# Sensor_PCI_Sch.net
KiCad netlist of a schematic drawn in Altium Designer
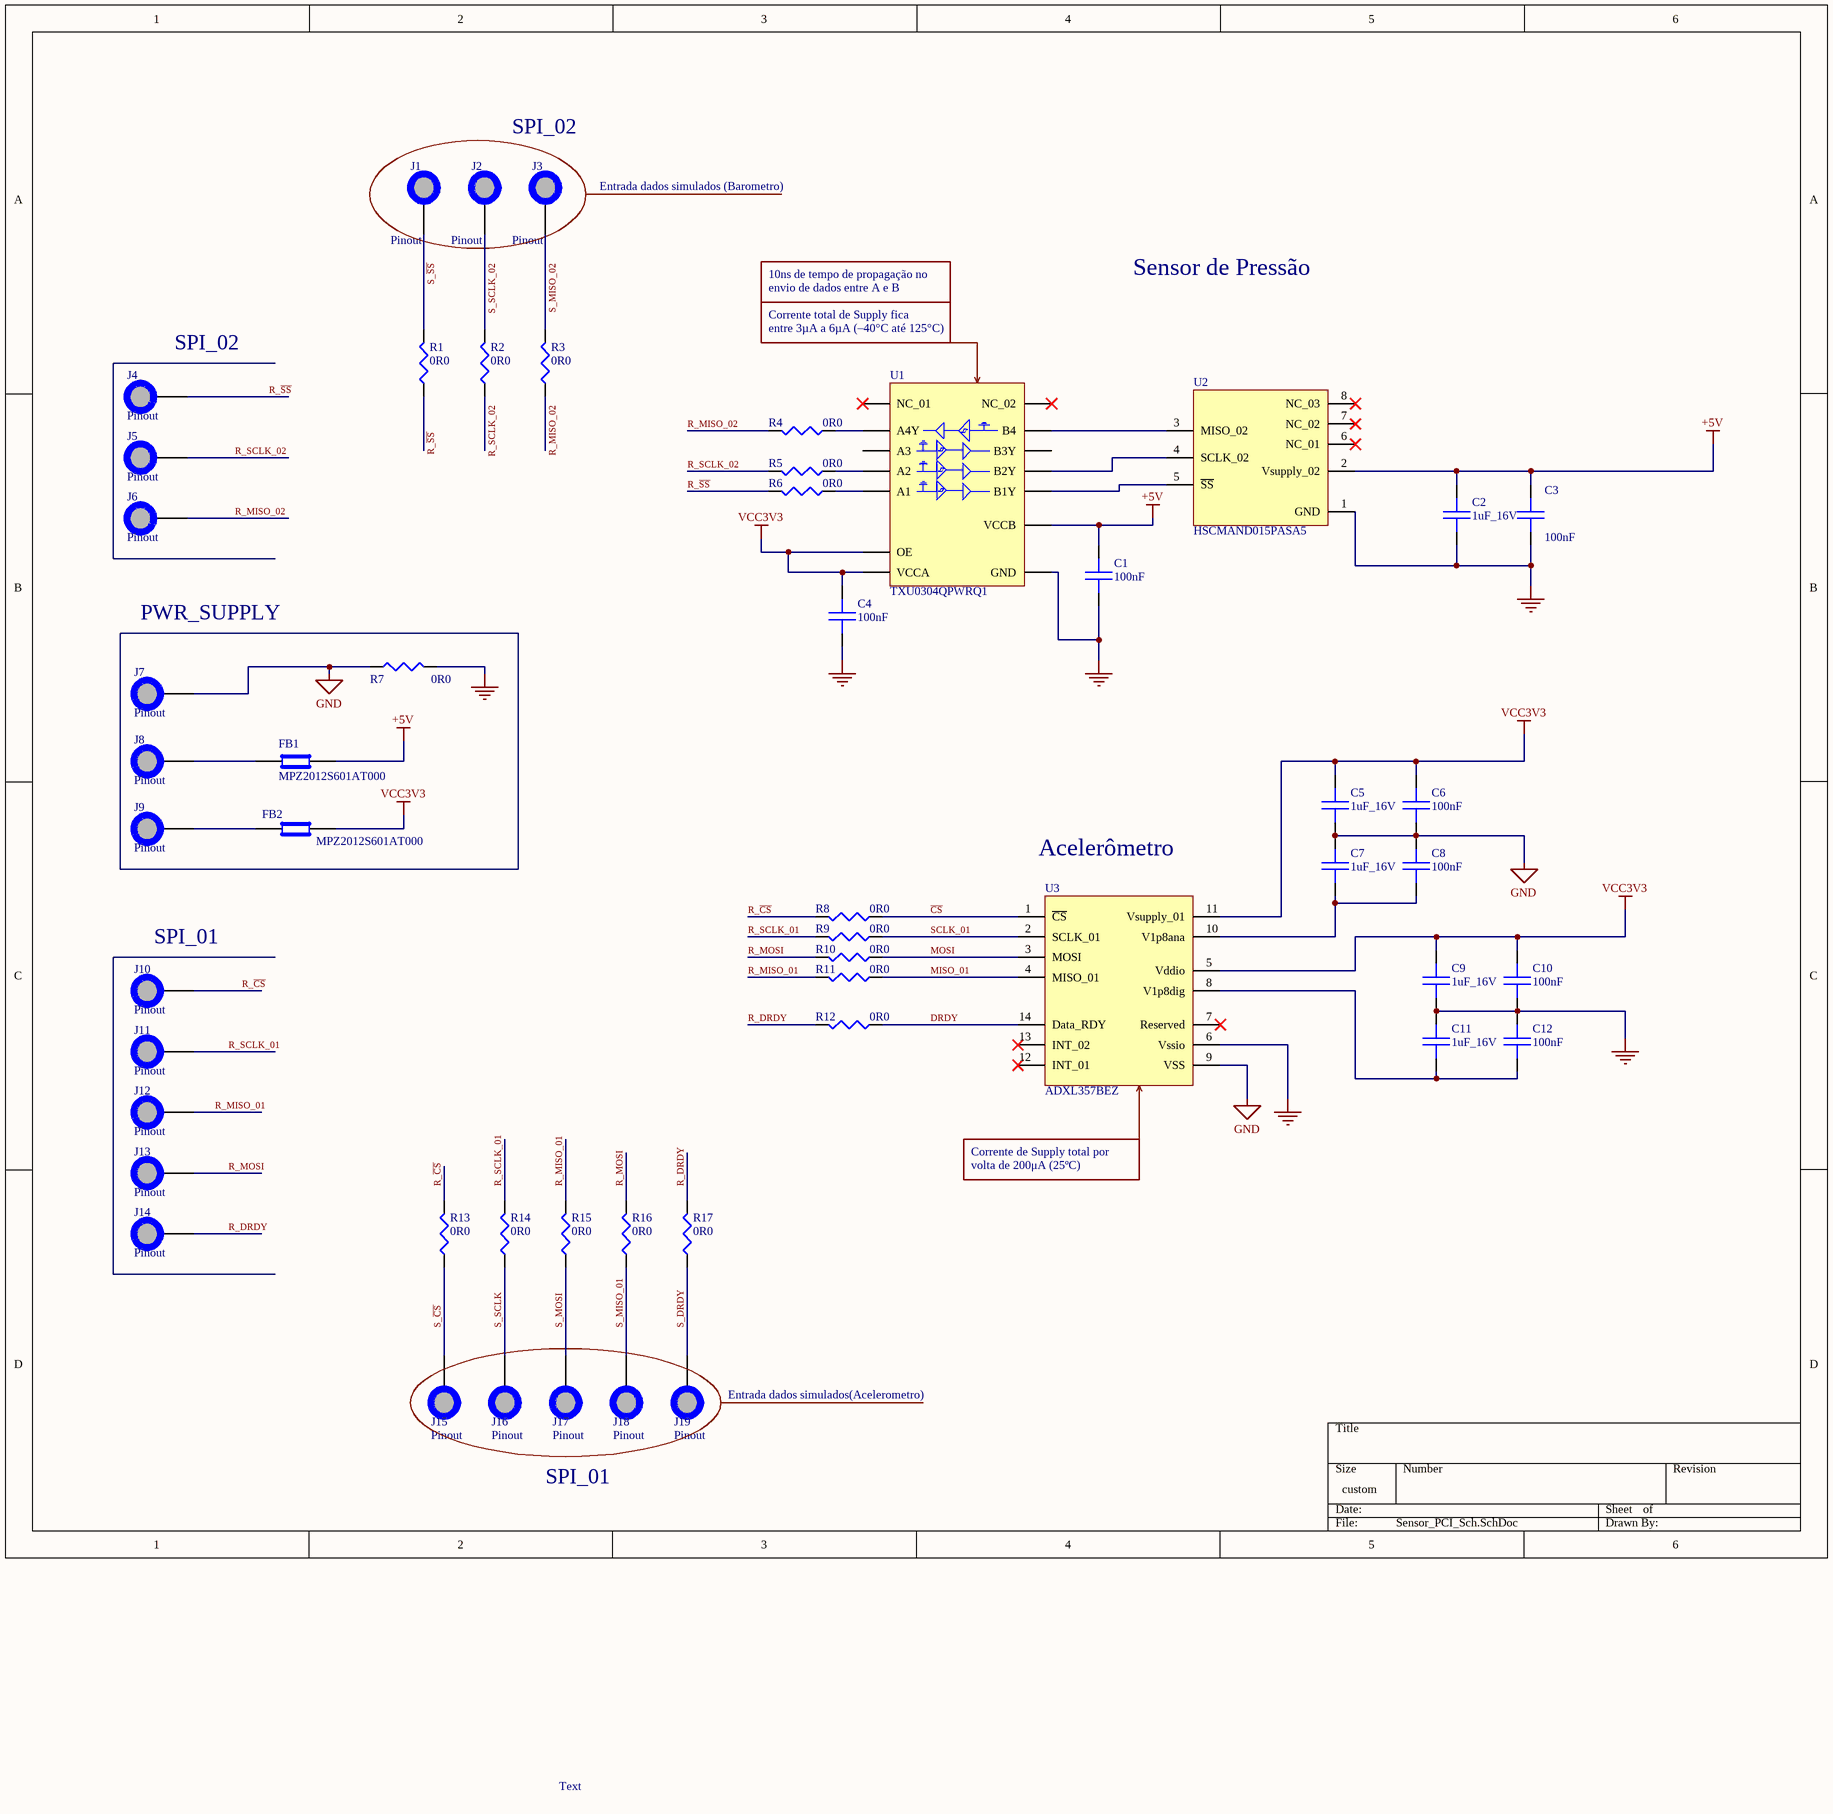
[diagram p0: Sensor_PCI_Sch.SchDoc]

(export (version "E")
  (design (tool "Eeschema 10.0.6"))
  (components
    (comp (ref "C1")
      (value "100nF")
      (footprint "CP_0805")
      (description "Cap Ceramic 0.1uF 50V X7R 20% Pad SMD 0805 150°C T/R")
      (fields
        (field (name "MANUFACTURER") "Vishay Vitramon")
        (field (name "MANUFACTURER PART NUMBER") "VJ0805Y104MXAMR")
      )
      (libsource (lib "Sensor_PCI_schlib") (part "C_0805_0.1uF"))
    )
    (comp (ref "C2")
      (value "1uF_16V")
      (footprint "C_1206")
      (description "Cap Ceramic 1uF 16V Y5V 20% SMD 1206 85°C Plastic T/R")
      (fields
        (field (name "MANUFACTURER") "Vishay Vitramon")
        (field (name "MANUFACTURER PART NUMBER") "VJ1206V105MXJTW1BC")
      )
      (libsource (lib "Sensor_PCI_schlib") (part "C_1206_1uF_16V"))
    )
    (comp (ref "C3")
      (value "100nF")
      (footprint "CP_0805")
      (description "Cap Ceramic 0.1uF 50V X7R 20% Pad SMD 0805 150°C T/R")
      (fields
        (field (name "MANUFACTURER") "Vishay Vitramon")
        (field (name "MANUFACTURER PART NUMBER") "VJ0805Y104MXAMR")
      )
      (libsource (lib "Sensor_PCI_schlib") (part "C_0805_0.1uF"))
    )
    (comp (ref "C4")
      (value "100nF")
      (footprint "CP_0805")
      (description "Cap Ceramic 0.1uF 50V X7R 20% Pad SMD 0805 150°C T/R")
      (fields
        (field (name "MANUFACTURER") "Vishay Vitramon")
        (field (name "MANUFACTURER PART NUMBER") "VJ0805Y104MXAMR")
      )
      (libsource (lib "Sensor_PCI_schlib") (part "C_0805_0.1uF"))
    )
    (comp (ref "C5")
      (value "1uF_16V")
      (footprint "C_1206")
      (description "Cap Ceramic 1uF 16V Y5V 20% SMD 1206 85°C Plastic T/R")
      (fields
        (field (name "MANUFACTURER") "Vishay Vitramon")
        (field (name "MANUFACTURER PART NUMBER") "VJ1206V105MXJTW1BC")
      )
      (libsource (lib "Sensor_PCI_schlib") (part "C_1206_1uF_16V"))
    )
    (comp (ref "C6")
      (value "100nF")
      (footprint "CP_0805")
      (description "Cap Ceramic 0.1uF 50V X7R 20% Pad SMD 0805 150°C T/R")
      (fields
        (field (name "MANUFACTURER") "Vishay Vitramon")
        (field (name "MANUFACTURER PART NUMBER") "VJ0805Y104MXAMR")
      )
      (libsource (lib "Sensor_PCI_schlib") (part "C_0805_0.1uF"))
    )
    (comp (ref "C7")
      (value "1uF_16V")
      (footprint "C_1206")
      (description "Cap Ceramic 1uF 16V Y5V 20% SMD 1206 85°C Plastic T/R")
      (fields
        (field (name "MANUFACTURER") "Vishay Vitramon")
        (field (name "MANUFACTURER PART NUMBER") "VJ1206V105MXJTW1BC")
      )
      (libsource (lib "Sensor_PCI_schlib") (part "C_1206_1uF_16V"))
    )
    (comp (ref "C8")
      (value "100nF")
      (footprint "CP_0805")
      (description "Cap Ceramic 0.1uF 50V X7R 20% Pad SMD 0805 150°C T/R")
      (fields
        (field (name "MANUFACTURER") "Vishay Vitramon")
        (field (name "MANUFACTURER PART NUMBER") "VJ0805Y104MXAMR")
      )
      (libsource (lib "Sensor_PCI_schlib") (part "C_0805_0.1uF"))
    )
    (comp (ref "C9")
      (value "1uF_16V")
      (footprint "C_1206")
      (description "Cap Ceramic 1uF 16V Y5V 20% SMD 1206 85°C Plastic T/R")
      (fields
        (field (name "MANUFACTURER") "Vishay Vitramon")
        (field (name "MANUFACTURER PART NUMBER") "VJ1206V105MXJTW1BC")
      )
      (libsource (lib "Sensor_PCI_schlib") (part "C_1206_1uF_16V"))
    )
    (comp (ref "C10")
      (value "100nF")
      (footprint "CP_0805")
      (description "Cap Ceramic 0.1uF 50V X7R 20% Pad SMD 0805 150°C T/R")
      (fields
        (field (name "MANUFACTURER") "Vishay Vitramon")
        (field (name "MANUFACTURER PART NUMBER") "VJ0805Y104MXAMR")
      )
      (libsource (lib "Sensor_PCI_schlib") (part "C_0805_0.1uF"))
    )
    (comp (ref "C11")
      (value "1uF_16V")
      (footprint "C_1206")
      (description "Cap Ceramic 1uF 16V Y5V 20% SMD 1206 85°C Plastic T/R")
      (fields
        (field (name "MANUFACTURER") "Vishay Vitramon")
        (field (name "MANUFACTURER PART NUMBER") "VJ1206V105MXJTW1BC")
      )
      (libsource (lib "Sensor_PCI_schlib") (part "C_1206_1uF_16V"))
    )
    (comp (ref "C12")
      (value "100nF")
      (footprint "CP_0805")
      (description "Cap Ceramic 0.1uF 50V X7R 20% Pad SMD 0805 150°C T/R")
      (fields
        (field (name "MANUFACTURER") "Vishay Vitramon")
        (field (name "MANUFACTURER PART NUMBER") "VJ0805Y104MXAMR")
      )
      (libsource (lib "Sensor_PCI_schlib") (part "C_0805_0.1uF"))
    )
    (comp (ref "FB1")
      (value "MPZ2012S601AT000")
      (footprint "CP_0805")
      (description "0805 600Ω ±25% DCR=0.1Ω 2A")
      (fields (field (name "MANUFACTURER") "TDK"))
      (libsource (lib "Sensor_PCI_schlib") (part "MPZ2012S601AT000"))
    )
    (comp (ref "FB2")
      (value "MPZ2012S601AT000")
      (footprint "CP_0805")
      (description "0805 600Ω ±25% DCR=0.1Ω 2A")
      (fields (field (name "MANUFACTURER") "TDK"))
      (libsource (lib "Sensor_PCI_schlib") (part "MPZ2012S601AT000"))
    )
    (comp (ref "J1")
      (value "Pinout")
      (footprint "Pinout")
      (libsource (lib "Sensor_PCI_schlib") (part "Pinout"))
    )
    (comp (ref "J2")
      (value "Pinout")
      (footprint "Pinout")
      (libsource (lib "Sensor_PCI_schlib") (part "Pinout"))
    )
    (comp (ref "J3")
      (value "Pinout")
      (footprint "Pinout")
      (libsource (lib "Sensor_PCI_schlib") (part "Pinout"))
    )
    (comp (ref "J4")
      (value "Pinout")
      (footprint "Pinout")
      (libsource (lib "Sensor_PCI_schlib") (part "Pinout"))
    )
    (comp (ref "J5")
      (value "Pinout")
      (footprint "Pinout")
      (libsource (lib "Sensor_PCI_schlib") (part "Pinout"))
    )
    (comp (ref "J6")
      (value "Pinout")
      (footprint "Pinout")
      (libsource (lib "Sensor_PCI_schlib") (part "Pinout"))
    )
    (comp (ref "J7")
      (value "Pinout")
      (footprint "Pinout")
      (libsource (lib "Sensor_PCI_schlib") (part "Pinout"))
    )
    (comp (ref "J8")
      (value "Pinout")
      (footprint "Pinout")
      (libsource (lib "Sensor_PCI_schlib") (part "Pinout"))
    )
    (comp (ref "J9")
      (value "Pinout")
      (footprint "Pinout")
      (libsource (lib "Sensor_PCI_schlib") (part "Pinout"))
    )
    (comp (ref "J10")
      (value "Pinout")
      (footprint "Pinout")
      (libsource (lib "Sensor_PCI_schlib") (part "Pinout"))
    )
    (comp (ref "J11")
      (value "Pinout")
      (footprint "Pinout")
      (libsource (lib "Sensor_PCI_schlib") (part "Pinout"))
    )
    (comp (ref "J12")
      (value "Pinout")
      (footprint "Pinout")
      (libsource (lib "Sensor_PCI_schlib") (part "Pinout"))
    )
    (comp (ref "J13")
      (value "Pinout")
      (footprint "Pinout")
      (libsource (lib "Sensor_PCI_schlib") (part "Pinout"))
    )
    (comp (ref "J14")
      (value "Pinout")
      (footprint "Pinout")
      (libsource (lib "Sensor_PCI_schlib") (part "Pinout"))
    )
    (comp (ref "J15")
      (value "Pinout")
      (footprint "Pinout")
      (libsource (lib "Sensor_PCI_schlib") (part "Pinout"))
    )
    (comp (ref "J16")
      (value "Pinout")
      (footprint "Pinout")
      (libsource (lib "Sensor_PCI_schlib") (part "Pinout"))
    )
    (comp (ref "J17")
      (value "Pinout")
      (footprint "Pinout")
      (libsource (lib "Sensor_PCI_schlib") (part "Pinout"))
    )
    (comp (ref "J18")
      (value "Pinout")
      (footprint "Pinout")
      (libsource (lib "Sensor_PCI_schlib") (part "Pinout"))
    )
    (comp (ref "J19")
      (value "Pinout")
      (footprint "Pinout")
      (libsource (lib "Sensor_PCI_schlib") (part "Pinout"))
    )
    (comp (ref "R1")
      (value "0R0")
      (footprint "R_0805")
      (description "CRCW Thick Film Commodity Chip Resistor Jumper 0805 Size 0 Ohm 0.125 W 2-Pin SMD Paper T/R")
      (fields
        (field (name "MANUFACTURER") "Vishay Dale")
        (field (name "MANUFACTURER PART NUMBER") "CRCW08050000Z0ECC")
      )
      (libsource (lib "Sensor_PCI_schlib") (part "Res_0805_0R0"))
    )
    (comp (ref "R2")
      (value "0R0")
      (footprint "R_0805")
      (description "CRCW Thick Film Commodity Chip Resistor Jumper 0805 Size 0 Ohm 0.125 W 2-Pin SMD Paper T/R")
      (fields
        (field (name "MANUFACTURER") "Vishay Dale")
        (field (name "MANUFACTURER PART NUMBER") "CRCW08050000Z0ECC")
      )
      (libsource (lib "Sensor_PCI_schlib") (part "Res_0805_0R0"))
    )
    (comp (ref "R3")
      (value "0R0")
      (footprint "R_0805")
      (description "CRCW Thick Film Commodity Chip Resistor Jumper 0805 Size 0 Ohm 0.125 W 2-Pin SMD Paper T/R")
      (fields
        (field (name "MANUFACTURER") "Vishay Dale")
        (field (name "MANUFACTURER PART NUMBER") "CRCW08050000Z0ECC")
      )
      (libsource (lib "Sensor_PCI_schlib") (part "Res_0805_0R0"))
    )
    (comp (ref "R4")
      (value "0R0")
      (footprint "R_0805")
      (description "CRCW Thick Film Commodity Chip Resistor Jumper 0805 Size 0 Ohm 0.125 W 2-Pin SMD Paper T/R")
      (fields
        (field (name "MANUFACTURER") "Vishay Dale")
        (field (name "MANUFACTURER PART NUMBER") "CRCW08050000Z0ECC")
      )
      (libsource (lib "Sensor_PCI_schlib") (part "Res_0805_0R0"))
    )
    (comp (ref "R5")
      (value "0R0")
      (footprint "R_0805")
      (description "CRCW Thick Film Commodity Chip Resistor Jumper 0805 Size 0 Ohm 0.125 W 2-Pin SMD Paper T/R")
      (fields
        (field (name "MANUFACTURER") "Vishay Dale")
        (field (name "MANUFACTURER PART NUMBER") "CRCW08050000Z0ECC")
      )
      (libsource (lib "Sensor_PCI_schlib") (part "Res_0805_0R0"))
    )
    (comp (ref "R6")
      (value "0R0")
      (footprint "R_0805")
      (description "CRCW Thick Film Commodity Chip Resistor Jumper 0805 Size 0 Ohm 0.125 W 2-Pin SMD Paper T/R")
      (fields
        (field (name "MANUFACTURER") "Vishay Dale")
        (field (name "MANUFACTURER PART NUMBER") "CRCW08050000Z0ECC")
      )
      (libsource (lib "Sensor_PCI_schlib") (part "Res_0805_0R0"))
    )
    (comp (ref "R7")
      (value "0R0")
      (footprint "R_0805")
      (description "CRCW Thick Film Commodity Chip Resistor Jumper 0805 Size 0 Ohm 0.125 W 2-Pin SMD Paper T/R")
      (fields
        (field (name "MANUFACTURER") "Vishay Dale")
        (field (name "MANUFACTURER PART NUMBER") "CRCW08050000Z0ECC")
      )
      (libsource (lib "Sensor_PCI_schlib") (part "Res_0805_0R0"))
    )
    (comp (ref "R8")
      (value "0R0")
      (footprint "R_0805")
      (description "CRCW Thick Film Commodity Chip Resistor Jumper 0805 Size 0 Ohm 0.125 W 2-Pin SMD Paper T/R")
      (fields
        (field (name "MANUFACTURER") "Vishay Dale")
        (field (name "MANUFACTURER PART NUMBER") "CRCW08050000Z0ECC")
      )
      (libsource (lib "Sensor_PCI_schlib") (part "Res_0805_0R0"))
    )
    (comp (ref "R9")
      (value "0R0")
      (footprint "R_0805")
      (description "CRCW Thick Film Commodity Chip Resistor Jumper 0805 Size 0 Ohm 0.125 W 2-Pin SMD Paper T/R")
      (fields
        (field (name "MANUFACTURER") "Vishay Dale")
        (field (name "MANUFACTURER PART NUMBER") "CRCW08050000Z0ECC")
      )
      (libsource (lib "Sensor_PCI_schlib") (part "Res_0805_0R0"))
    )
    (comp (ref "R10")
      (value "0R0")
      (footprint "R_0805")
      (description "CRCW Thick Film Commodity Chip Resistor Jumper 0805 Size 0 Ohm 0.125 W 2-Pin SMD Paper T/R")
      (fields
        (field (name "MANUFACTURER") "Vishay Dale")
        (field (name "MANUFACTURER PART NUMBER") "CRCW08050000Z0ECC")
      )
      (libsource (lib "Sensor_PCI_schlib") (part "Res_0805_0R0"))
    )
    (comp (ref "R11")
      (value "0R0")
      (footprint "R_0805")
      (description "CRCW Thick Film Commodity Chip Resistor Jumper 0805 Size 0 Ohm 0.125 W 2-Pin SMD Paper T/R")
      (fields
        (field (name "MANUFACTURER") "Vishay Dale")
        (field (name "MANUFACTURER PART NUMBER") "CRCW08050000Z0ECC")
      )
      (libsource (lib "Sensor_PCI_schlib") (part "Res_0805_0R0"))
    )
    (comp (ref "R12")
      (value "0R0")
      (footprint "R_0805")
      (description "CRCW Thick Film Commodity Chip Resistor Jumper 0805 Size 0 Ohm 0.125 W 2-Pin SMD Paper T/R")
      (fields
        (field (name "MANUFACTURER") "Vishay Dale")
        (field (name "MANUFACTURER PART NUMBER") "CRCW08050000Z0ECC")
      )
      (libsource (lib "Sensor_PCI_schlib") (part "Res_0805_0R0"))
    )
    (comp (ref "R13")
      (value "0R0")
      (footprint "R_0805")
      (description "CRCW Thick Film Commodity Chip Resistor Jumper 0805 Size 0 Ohm 0.125 W 2-Pin SMD Paper T/R")
      (fields
        (field (name "MANUFACTURER") "Vishay Dale")
        (field (name "MANUFACTURER PART NUMBER") "CRCW08050000Z0ECC")
      )
      (libsource (lib "Sensor_PCI_schlib") (part "Res_0805_0R0"))
    )
    (comp (ref "R14")
      (value "0R0")
      (footprint "R_0805")
      (description "CRCW Thick Film Commodity Chip Resistor Jumper 0805 Size 0 Ohm 0.125 W 2-Pin SMD Paper T/R")
      (fields
        (field (name "MANUFACTURER") "Vishay Dale")
        (field (name "MANUFACTURER PART NUMBER") "CRCW08050000Z0ECC")
      )
      (libsource (lib "Sensor_PCI_schlib") (part "Res_0805_0R0"))
    )
    (comp (ref "R15")
      (value "0R0")
      (footprint "R_0805")
      (description "CRCW Thick Film Commodity Chip Resistor Jumper 0805 Size 0 Ohm 0.125 W 2-Pin SMD Paper T/R")
      (fields
        (field (name "MANUFACTURER") "Vishay Dale")
        (field (name "MANUFACTURER PART NUMBER") "CRCW08050000Z0ECC")
      )
      (libsource (lib "Sensor_PCI_schlib") (part "Res_0805_0R0"))
    )
    (comp (ref "R16")
      (value "0R0")
      (footprint "R_0805")
      (description "CRCW Thick Film Commodity Chip Resistor Jumper 0805 Size 0 Ohm 0.125 W 2-Pin SMD Paper T/R")
      (fields
        (field (name "MANUFACTURER") "Vishay Dale")
        (field (name "MANUFACTURER PART NUMBER") "CRCW08050000Z0ECC")
      )
      (libsource (lib "Sensor_PCI_schlib") (part "Res_0805_0R0"))
    )
    (comp (ref "R17")
      (value "0R0")
      (footprint "R_0805")
      (description "CRCW Thick Film Commodity Chip Resistor Jumper 0805 Size 0 Ohm 0.125 W 2-Pin SMD Paper T/R")
      (fields
        (field (name "MANUFACTURER") "Vishay Dale")
        (field (name "MANUFACTURER PART NUMBER") "CRCW08050000Z0ECC")
      )
      (libsource (lib "Sensor_PCI_schlib") (part "Res_0805_0R0"))
    )
    (comp (ref "U1")
      (value "TXU0304QPWRQ1")
      (footprint "TSSOP-PW")
      (description "Automotive four channel unidirectional level shifter 14-TSSOP -40 to 125")
      (fields (field (name "MANUFACTURER") "Texas Instruments"))
      (libsource (lib "Sensor_PCI_schlib") (part "Tradutor fixo de Tensão-SPI"))
    )
    (comp (ref "U2")
      (value "HSCMAND015PASA5")
      (footprint "SMT_08_2.54mm")
      (description "Board Mount Pressure Sensors SMT, Single Ax Barbed Absolute, 5V")
      (fields (field (name "MANUFACTURER") "Honeywell Sensing & Control"))
      (libsource (lib "Sensor_PCI_schlib") (part "Sensor_Pressão"))
    )
    (comp (ref "U3")
      (value "ADXL357BEZ")
      (footprint "Quad_14_1.2mm")
      (description "Accelerometer Tri-axis Digital Accel")
      (fields (field (name "MANUFACTURER") "Analog Devices"))
      (libsource (lib "Sensor_PCI_schlib") (part "Acelerômetro"))
    )
  )
  (nets
    (net (code "1") (name "+5V") (class "Default")
      (node (ref "C1") (pin "2") (pinfunction "2_2") (pintype "passive"))
      (node (ref "C2") (pin "1") (pinfunction "3_1") (pintype "passive"))
      (node (ref "C3") (pin "2") (pinfunction "2_2") (pintype "passive"))
      (node (ref "FB1") (pin "2") (pinfunction "2_2") (pintype "passive"))
      (node (ref "U1") (pin "14") (pinfunction "VCCB_14") (pintype "passive"))
      (node (ref "U2") (pin "2") (pinfunction "Vsupply_02_2") (pintype "passive"))
    )
    (net (code "2") (name "/DRDY") (class "Default")
      (node (ref "R12") (pin "1") (pinfunction "1_1") (pintype "passive"))
      (node (ref "U3") (pin "14") (pinfunction "Data_RDY_14") (pintype "passive"))
    )
    (net (code "3") (name "/MISO_01") (class "Default")
      (node (ref "R11") (pin "1") (pinfunction "1_1") (pintype "passive"))
      (node (ref "U3") (pin "4") (pinfunction "MISO_01_4") (pintype "passive"))
    )
    (net (code "4") (name "/MOSI") (class "Default")
      (node (ref "R10") (pin "1") (pinfunction "1_1") (pintype "passive"))
      (node (ref "U3") (pin "3") (pinfunction "MOSI_3") (pintype "passive"))
    )
    (net (code "5") (name "/R_DRDY") (class "Default")
      (node (ref "J14") (pin "1") (pinfunction "1_1") (pintype "passive"))
      (node (ref "R12") (pin "2") (pinfunction "2_2") (pintype "passive"))
      (node (ref "R17") (pin "2") (pinfunction "2_2") (pintype "passive"))
    )
    (net (code "6") (name "/R_MISO_01") (class "Default")
      (node (ref "J12") (pin "1") (pinfunction "1_1") (pintype "passive"))
      (node (ref "R11") (pin "2") (pinfunction "2_2") (pintype "passive"))
      (node (ref "R15") (pin "2") (pinfunction "2_2") (pintype "passive"))
    )
    (net (code "7") (name "/R_MISO_02") (class "Default")
      (node (ref "J6") (pin "1") (pinfunction "1_1") (pintype "passive"))
      (node (ref "R3") (pin "1") (pinfunction "1_1") (pintype "passive"))
      (node (ref "R4") (pin "2") (pinfunction "2_2") (pintype "passive"))
    )
    (net (code "8") (name "/R_MOSI") (class "Default")
      (node (ref "J13") (pin "1") (pinfunction "1_1") (pintype "passive"))
      (node (ref "R10") (pin "2") (pinfunction "2_2") (pintype "passive"))
      (node (ref "R16") (pin "2") (pinfunction "2_2") (pintype "passive"))
    )
    (net (code "9") (name "/R_SCLK_01") (class "Default")
      (node (ref "J11") (pin "1") (pinfunction "1_1") (pintype "passive"))
      (node (ref "R14") (pin "2") (pinfunction "2_2") (pintype "passive"))
      (node (ref "R9") (pin "2") (pinfunction "2_2") (pintype "passive"))
    )
    (net (code "10") (name "/R_SCLK_02") (class "Default")
      (node (ref "J5") (pin "1") (pinfunction "1_1") (pintype "passive"))
      (node (ref "R2") (pin "1") (pinfunction "1_1") (pintype "passive"))
      (node (ref "R5") (pin "2") (pinfunction "2_2") (pintype "passive"))
    )
    (net (code "11") (name "/R_~{CS}") (class "Default")
      (node (ref "J10") (pin "1") (pinfunction "1_1") (pintype "passive"))
      (node (ref "R13") (pin "2") (pinfunction "2_2") (pintype "passive"))
      (node (ref "R8") (pin "2") (pinfunction "2_2") (pintype "passive"))
    )
    (net (code "12") (name "/R_~{SS}") (class "Default")
      (node (ref "J4") (pin "1") (pinfunction "1_1") (pintype "passive"))
      (node (ref "R1") (pin "1") (pinfunction "1_1") (pintype "passive"))
      (node (ref "R6") (pin "2") (pinfunction "2_2") (pintype "passive"))
    )
    (net (code "13") (name "/SCLK_01") (class "Default")
      (node (ref "R9") (pin "1") (pinfunction "1_1") (pintype "passive"))
      (node (ref "U3") (pin "2") (pinfunction "SCLK_01_2") (pintype "passive"))
    )
    (net (code "14") (name "/S_DRDY") (class "Default")
      (node (ref "J19") (pin "1") (pinfunction "1_1") (pintype "passive"))
      (node (ref "R17") (pin "1") (pinfunction "1_1") (pintype "passive"))
    )
    (net (code "15") (name "/S_MISO_01") (class "Default")
      (node (ref "J18") (pin "1") (pinfunction "1_1") (pintype "passive"))
      (node (ref "R16") (pin "1") (pinfunction "1_1") (pintype "passive"))
    )
    (net (code "16") (name "/S_MISO_02") (class "Default")
      (node (ref "J3") (pin "1") (pinfunction "1_1") (pintype "passive"))
      (node (ref "R3") (pin "2") (pinfunction "2_2") (pintype "passive"))
    )
    (net (code "17") (name "/S_MOSI") (class "Default")
      (node (ref "J17") (pin "1") (pinfunction "1_1") (pintype "passive"))
      (node (ref "R15") (pin "1") (pinfunction "1_1") (pintype "passive"))
    )
    (net (code "18") (name "/S_SCLK") (class "Default")
      (node (ref "J16") (pin "1") (pinfunction "1_1") (pintype "passive"))
      (node (ref "R14") (pin "1") (pinfunction "1_1") (pintype "passive"))
    )
    (net (code "19") (name "/S_SCLK_02") (class "Default")
      (node (ref "J2") (pin "1") (pinfunction "1_1") (pintype "passive"))
      (node (ref "R2") (pin "2") (pinfunction "2_2") (pintype "passive"))
    )
    (net (code "20") (name "/S_~{CS}") (class "Default")
      (node (ref "J15") (pin "1") (pinfunction "1_1") (pintype "passive"))
      (node (ref "R13") (pin "1") (pinfunction "1_1") (pintype "passive"))
    )
    (net (code "21") (name "/S_~{SS}") (class "Default")
      (node (ref "J1") (pin "1") (pinfunction "1_1") (pintype "passive"))
      (node (ref "R1") (pin "2") (pinfunction "2_2") (pintype "passive"))
    )
    (net (code "22") (name "/~{CS}") (class "Default")
      (node (ref "R8") (pin "1") (pinfunction "1_1") (pintype "passive"))
      (node (ref "U3") (pin "1") (pinfunction "~{CS}_1") (pintype "passive"))
    )
    (net (code "23") (name "GND") (class "Default")
      (node (ref "C1") (pin "1") (pinfunction "1_1") (pintype "passive"))
      (node (ref "C10") (pin "1") (pinfunction "1_1") (pintype "passive"))
      (node (ref "C11") (pin "1") (pinfunction "3_1") (pintype "passive"))
      (node (ref "C12") (pin "2") (pinfunction "2_2") (pintype "passive"))
      (node (ref "C2") (pin "2") (pinfunction "4_2") (pintype "passive"))
      (node (ref "C3") (pin "1") (pinfunction "1_1") (pintype "passive"))
      (node (ref "C4") (pin "1") (pinfunction "1_1") (pintype "passive"))
      (node (ref "C5") (pin "2") (pinfunction "4_2") (pintype "passive"))
      (node (ref "C6") (pin "1") (pinfunction "1_1") (pintype "passive"))
      (node (ref "C7") (pin "1") (pinfunction "3_1") (pintype "passive"))
      (node (ref "C8") (pin "2") (pinfunction "2_2") (pintype "passive"))
      (node (ref "C9") (pin "2") (pinfunction "4_2") (pintype "passive"))
      (node (ref "J7") (pin "1") (pinfunction "1_1") (pintype "passive"))
      (node (ref "R7") (pin "1") (pinfunction "1_1") (pintype "passive"))
      (node (ref "R7") (pin "2") (pinfunction "2_2") (pintype "passive"))
      (node (ref "U1") (pin "7") (pinfunction "GND_7") (pintype "passive"))
      (node (ref "U2") (pin "1") (pinfunction "GND_1") (pintype "passive"))
      (node (ref "U3") (pin "6") (pinfunction "Vssio_6") (pintype "passive"))
      (node (ref "U3") (pin "9") (pinfunction "VSS_9") (pintype "passive"))
    )
    (net (code "24") (name "Net-(C7-4)") (class "Default")
      (node (ref "C7") (pin "2") (pinfunction "4_2") (pintype "passive"))
      (node (ref "C8") (pin "1") (pinfunction "1_1") (pintype "passive"))
      (node (ref "U3") (pin "10") (pinfunction "V1p8ana_10") (pintype "passive"))
    )
    (net (code "25") (name "Net-(C11-4)") (class "Default")
      (node (ref "C11") (pin "2") (pinfunction "4_2") (pintype "passive"))
      (node (ref "C12") (pin "1") (pinfunction "1_1") (pintype "passive"))
      (node (ref "U3") (pin "8") (pinfunction "V1p8dig_8") (pintype "passive"))
    )
    (net (code "26") (name "Net-(FB1-Pad1)") (class "Default")
      (node (ref "FB1") (pin "1") (pinfunction "1_1") (pintype "passive"))
      (node (ref "J8") (pin "1") (pinfunction "1_1") (pintype "passive"))
    )
    (net (code "27") (name "Net-(FB2-Pad1)") (class "Default")
      (node (ref "FB2") (pin "1") (pinfunction "1_1") (pintype "passive"))
      (node (ref "J9") (pin "1") (pinfunction "1_1") (pintype "passive"))
    )
    (net (code "28") (name "Net-(U1-A1)") (class "Default")
      (node (ref "R6") (pin "1") (pinfunction "1_1") (pintype "passive"))
      (node (ref "U1") (pin "2") (pinfunction "A1_2") (pintype "passive"))
    )
    (net (code "29") (name "Net-(U1-A2)") (class "Default")
      (node (ref "R5") (pin "1") (pinfunction "1_1") (pintype "passive"))
      (node (ref "U1") (pin "3") (pinfunction "A2_3") (pintype "passive"))
    )
    (net (code "30") (name "Net-(U1-A4Y)") (class "Default")
      (node (ref "R4") (pin "1") (pinfunction "1_1") (pintype "passive"))
      (node (ref "U1") (pin "5") (pinfunction "A4Y_5") (pintype "passive"))
    )
    (net (code "31") (name "Net-(U1-B1Y)") (class "Default")
      (node (ref "U1") (pin "13") (pinfunction "B1Y_13") (pintype "passive"))
      (node (ref "U2") (pin "5") (pinfunction "~{SS}_5") (pintype "passive"))
    )
    (net (code "32") (name "Net-(U1-B2Y)") (class "Default")
      (node (ref "U1") (pin "12") (pinfunction "B2Y_12") (pintype "passive"))
      (node (ref "U2") (pin "4") (pinfunction "SCLK_02_4") (pintype "passive"))
    )
    (net (code "33") (name "Net-(U1-B4)") (class "Default")
      (node (ref "U1") (pin "10") (pinfunction "B4_10") (pintype "passive"))
      (node (ref "U2") (pin "3") (pinfunction "MISO_02_3") (pintype "passive"))
    )
    (net (code "34") (name "VCC3V3") (class "Default")
      (node (ref "C10") (pin "2") (pinfunction "2_2") (pintype "passive"))
      (node (ref "C4") (pin "2") (pinfunction "2_2") (pintype "passive"))
      (node (ref "C5") (pin "1") (pinfunction "3_1") (pintype "passive"))
      (node (ref "C6") (pin "2") (pinfunction "2_2") (pintype "passive"))
      (node (ref "C9") (pin "1") (pinfunction "3_1") (pintype "passive"))
      (node (ref "FB2") (pin "2") (pinfunction "2_2") (pintype "passive"))
      (node (ref "U1") (pin "1") (pinfunction "VCCA_1") (pintype "passive"))
      (node (ref "U1") (pin "8") (pinfunction "OE_8") (pintype "passive"))
      (node (ref "U3") (pin "11") (pinfunction "Vsupply_01_11") (pintype "passive"))
      (node (ref "U3") (pin "5") (pinfunction "Vddio_5") (pintype "passive"))
    )
    (net (code "35") (name "unconnected-(U1-A3-Pad4)") (class "Default")
      (node (ref "U1") (pin "4") (pinfunction "A3_4") (pintype "passive"))
    )
    (net (code "36") (name "unconnected-(U1-B3Y-Pad11)") (class "Default")
      (node (ref "U1") (pin "11") (pinfunction "B3Y_11") (pintype "passive"))
    )
    (net (code "37") (name "unconnected-(U1-NC_01-Pad6)") (class "Default")
      (node (ref "U1") (pin "6") (pinfunction "NC_01_6") (pintype "passive+no_connect"))
    )
    (net (code "38") (name "unconnected-(U1-NC_02-Pad9)") (class "Default")
      (node (ref "U1") (pin "9") (pinfunction "NC_02_9") (pintype "passive+no_connect"))
    )
    (net (code "39") (name "unconnected-(U2-NC_01-Pad6)") (class "Default")
      (node (ref "U2") (pin "6") (pinfunction "NC_01_6") (pintype "passive+no_connect"))
    )
    (net (code "40") (name "unconnected-(U2-NC_02-Pad7)") (class "Default")
      (node (ref "U2") (pin "7") (pinfunction "NC_02_7") (pintype "passive+no_connect"))
    )
    (net (code "41") (name "unconnected-(U2-NC_03-Pad8)") (class "Default")
      (node (ref "U2") (pin "8") (pinfunction "NC_03_8") (pintype "passive+no_connect"))
    )
    (net (code "42") (name "unconnected-(U3-INT_01-Pad12)") (class "Default")
      (node (ref "U3") (pin "12") (pinfunction "INT_01_12") (pintype "passive+no_connect"))
    )
    (net (code "43") (name "unconnected-(U3-INT_02-Pad13)") (class "Default")
      (node (ref "U3") (pin "13") (pinfunction "INT_02_13") (pintype "passive+no_connect"))
    )
    (net (code "44") (name "unconnected-(U3-Reserved-Pad7)") (class "Default")
      (node (ref "U3") (pin "7") (pinfunction "Reserved_7") (pintype "passive+no_connect"))
    )
  )
)
